# HLF356amp-revisi01.net
KiCad netlist of a schematic drawn in EAGLE
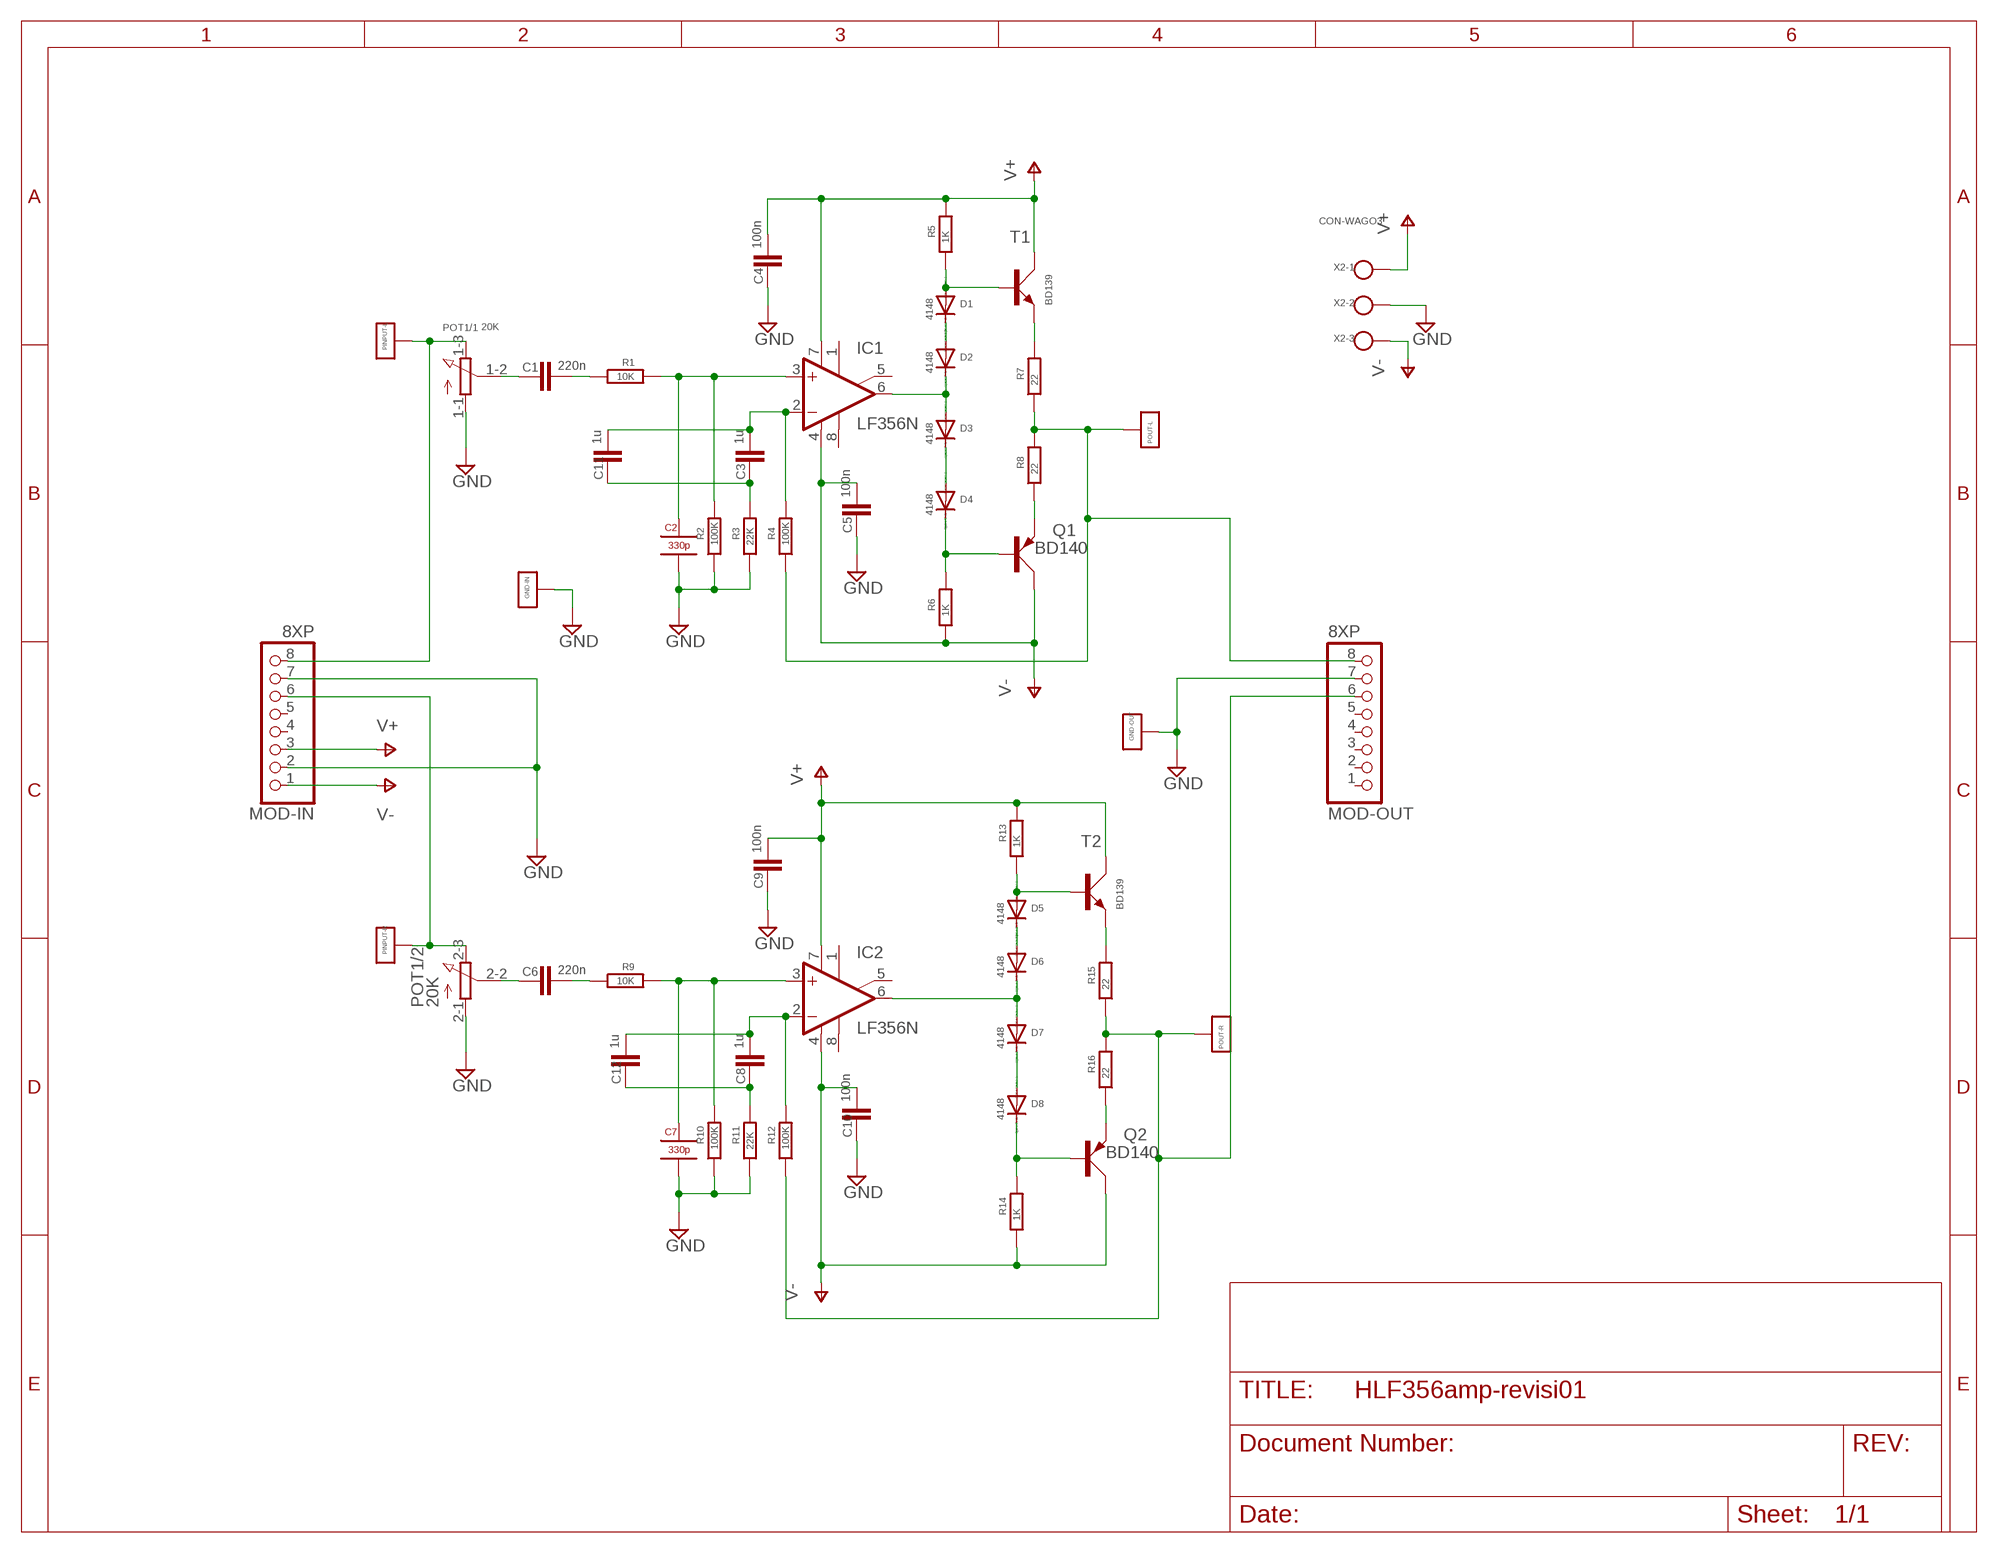
[diagram p0: schematic, sheet 1]

(export (version "E")
  (design (tool "Eeschema 10.0.6"))
  (components
    (comp (ref "C1")
      (value "220n")
      (footprint "eagle-import:C050-025X075")
      (libsource (lib "eagle-import") (part "C-EU050-025X075"))
    )
    (comp (ref "C2")
      (value "330p")
      (footprint "eagle-import:RIFAEVOX")
      (libsource (lib "eagle-import") (part "RIFAEVOXPFR5"))
    )
    (comp (ref "C3")
      (value "1u")
      (footprint "eagle-import:C150-072X183")
      (libsource (lib "eagle-import") (part "C-EU150-072X183"))
    )
    (comp (ref "C4")
      (value "100n")
      (footprint "eagle-import:C050-025X075")
      (libsource (lib "eagle-import") (part "C-EU050-025X075"))
    )
    (comp (ref "C5")
      (value "100n")
      (footprint "eagle-import:C050-025X075")
      (libsource (lib "eagle-import") (part "C-EU050-025X075"))
    )
    (comp (ref "C6")
      (value "220n")
      (footprint "eagle-import:C050-025X075")
      (libsource (lib "eagle-import") (part "C-EU050-025X075"))
    )
    (comp (ref "C7")
      (value "330p")
      (footprint "eagle-import:RIFAEVOX")
      (libsource (lib "eagle-import") (part "RIFAEVOXPFR5"))
    )
    (comp (ref "C8")
      (value "1u")
      (footprint "eagle-import:C150-072X183")
      (libsource (lib "eagle-import") (part "C-EU150-072X183"))
    )
    (comp (ref "C9")
      (value "100n")
      (footprint "eagle-import:C050-025X075")
      (libsource (lib "eagle-import") (part "C-EU050-025X075"))
    )
    (comp (ref "C10")
      (value "100n")
      (footprint "eagle-import:C050-025X075")
      (libsource (lib "eagle-import") (part "C-EU050-025X075"))
    )
    (comp (ref "C11")
      (value "1u")
      (footprint "eagle-import:C050-075X075")
      (libsource (lib "eagle-import") (part "C-EU050-075X075"))
    )
    (comp (ref "C12")
      (value "1u")
      (footprint "eagle-import:C050-075X075")
      (libsource (lib "eagle-import") (part "C-EU050-075X075"))
    )
    (comp (ref "D1")
      (value "4148")
      (footprint "eagle-import:DO35-7")
      (libsource (lib "eagle-import") (part "1N4148DO35-7"))
    )
    (comp (ref "D2")
      (value "4148")
      (footprint "eagle-import:DO35-7")
      (libsource (lib "eagle-import") (part "1N4148DO35-7"))
    )
    (comp (ref "D3")
      (value "4148")
      (footprint "eagle-import:DO35-7")
      (libsource (lib "eagle-import") (part "1N4148DO35-7"))
    )
    (comp (ref "D4")
      (value "4148")
      (footprint "eagle-import:DO35-7")
      (libsource (lib "eagle-import") (part "1N4148DO35-7"))
    )
    (comp (ref "D5")
      (value "4148")
      (footprint "eagle-import:DO35-7")
      (libsource (lib "eagle-import") (part "1N4148DO35-7"))
    )
    (comp (ref "D6")
      (value "4148")
      (footprint "eagle-import:DO35-7")
      (libsource (lib "eagle-import") (part "1N4148DO35-7"))
    )
    (comp (ref "D7")
      (value "4148")
      (footprint "eagle-import:DO35-7")
      (libsource (lib "eagle-import") (part "1N4148DO35-7"))
    )
    (comp (ref "D8")
      (value "4148")
      (footprint "eagle-import:DO35-7")
      (libsource (lib "eagle-import") (part "1N4148DO35-7"))
    )
    (comp (ref "GND-IN")
      (value "PIN-BIG1X")
      (footprint "eagle-import:PIN-BIG")
      (libsource (lib "eagle-import") (part "PIN-BIG1X"))
    )
    (comp (ref "GND-OUT")
      (value "PIN-BIG1X")
      (footprint "eagle-import:PIN-BIG")
      (libsource (lib "eagle-import") (part "PIN-BIG1X"))
    )
    (comp (ref "IC1")
      (value "LF356N")
      (footprint "eagle-import:DIL08")
      (libsource (lib "eagle-import") (part "LF356N"))
    )
    (comp (ref "IC2")
      (value "LF356N")
      (footprint "eagle-import:DIL08")
      (libsource (lib "eagle-import") (part "LF356N"))
    )
    (comp (ref "MOD-IN")
      (value "8XP")
      (footprint "eagle-import:1X08-BIG")
      (libsource (lib "eagle-import") (part "PINHD-1X8BIG"))
    )
    (comp (ref "MOD-OUT")
      (value "8XP")
      (footprint "eagle-import:1X08-BIG")
      (libsource (lib "eagle-import") (part "PINHD-1X8BIG"))
    )
    (comp (ref "PINPUT-L")
      (value "PIN-BIG1X")
      (footprint "eagle-import:PIN-BIG")
      (libsource (lib "eagle-import") (part "PIN-BIG1X"))
    )
    (comp (ref "PINPUT-R")
      (value "PIN-BIG1X")
      (footprint "eagle-import:PIN-BIG")
      (libsource (lib "eagle-import") (part "PIN-BIG1X"))
    )
    (comp (ref "POT1")
      (value "20K")
      (footprint "eagle-import:3RP_1610G")
      (libsource (lib "eagle-import") (part "3RP/1610G"))
    )
    (comp (ref "POUT-L")
      (value "PIN-BIG1X")
      (footprint "eagle-import:PIN-BIG")
      (libsource (lib "eagle-import") (part "PIN-BIG1X"))
    )
    (comp (ref "POUT-R")
      (value "PIN-BIG1X")
      (footprint "eagle-import:PIN-BIG")
      (libsource (lib "eagle-import") (part "PIN-BIG1X"))
    )
    (comp (ref "Q1")
      (value "BD140")
      (footprint "eagle-import:TO126AV")
      (libsource (lib "eagle-import") (part "BD140"))
    )
    (comp (ref "Q2")
      (value "BD140")
      (footprint "eagle-import:TO126AV")
      (libsource (lib "eagle-import") (part "BD140"))
    )
    (comp (ref "R1")
      (value "10K")
      (footprint "eagle-import:0204_7")
      (libsource (lib "eagle-import") (part "R-EU_0204/7"))
    )
    (comp (ref "R2")
      (value "100K")
      (footprint "eagle-import:0204_7")
      (libsource (lib "eagle-import") (part "R-EU_0204/7"))
    )
    (comp (ref "R3")
      (value "22K")
      (footprint "eagle-import:0204_7")
      (libsource (lib "eagle-import") (part "R-EU_0204/7"))
    )
    (comp (ref "R4")
      (value "100K")
      (footprint "eagle-import:0204_7")
      (libsource (lib "eagle-import") (part "R-EU_0204/7"))
    )
    (comp (ref "R5")
      (value "1K")
      (footprint "eagle-import:0204_7")
      (libsource (lib "eagle-import") (part "R-EU_0204/7"))
    )
    (comp (ref "R6")
      (value "1K")
      (footprint "eagle-import:0204_7")
      (libsource (lib "eagle-import") (part "R-EU_0204/7"))
    )
    (comp (ref "R7")
      (value "22")
      (footprint "eagle-import:0204_7")
      (libsource (lib "eagle-import") (part "R-EU_0204/7"))
    )
    (comp (ref "R8")
      (value "22")
      (footprint "eagle-import:0204_7")
      (libsource (lib "eagle-import") (part "R-EU_0204/7"))
    )
    (comp (ref "R9")
      (value "10K")
      (footprint "eagle-import:0204_7")
      (libsource (lib "eagle-import") (part "R-EU_0204/7"))
    )
    (comp (ref "R10")
      (value "100K")
      (footprint "eagle-import:0204_7")
      (libsource (lib "eagle-import") (part "R-EU_0204/7"))
    )
    (comp (ref "R11")
      (value "22K")
      (footprint "eagle-import:0204_7")
      (libsource (lib "eagle-import") (part "R-EU_0204/7"))
    )
    (comp (ref "R12")
      (value "100K")
      (footprint "eagle-import:0204_7")
      (libsource (lib "eagle-import") (part "R-EU_0204/7"))
    )
    (comp (ref "R13")
      (value "1K")
      (footprint "eagle-import:0204_7")
      (libsource (lib "eagle-import") (part "R-EU_0204/7"))
    )
    (comp (ref "R14")
      (value "1K")
      (footprint "eagle-import:0204_7")
      (libsource (lib "eagle-import") (part "R-EU_0204/7"))
    )
    (comp (ref "R15")
      (value "22")
      (footprint "eagle-import:0204_7")
      (libsource (lib "eagle-import") (part "R-EU_0204/7"))
    )
    (comp (ref "R16")
      (value "22")
      (footprint "eagle-import:0204_7")
      (libsource (lib "eagle-import") (part "R-EU_0204/7"))
    )
    (comp (ref "T1")
      (value "BD139")
      (footprint "eagle-import:TO126AV")
      (libsource (lib "eagle-import") (part "BD139"))
    )
    (comp (ref "T2")
      (value "BD139")
      (footprint "eagle-import:TO126AV")
      (libsource (lib "eagle-import") (part "BD139"))
    )
    (comp (ref "X2")
      (value "CON-WAGO3")
      (footprint "eagle-import:W237-103")
      (fields (field (name "MPN") "237-103"))
      (libsource (lib "eagle-import") (part "W237-103"))
    )
  )
  (nets
    (net (code "1") (name "GND") (class "Default")
      (node (ref "C10") (pin "1") (pinfunction "1_1") (pintype "passive"))
      (node (ref "C2") (pin "P$2") (pinfunction "P$2_P$2") (pintype "bidirectional"))
      (node (ref "C4") (pin "1") (pinfunction "1_1") (pintype "passive"))
      (node (ref "C5") (pin "1") (pinfunction "1_1") (pintype "passive"))
      (node (ref "C7") (pin "P$2") (pinfunction "P$2_P$2") (pintype "bidirectional"))
      (node (ref "C9") (pin "1") (pinfunction "1_1") (pintype "passive"))
      (node (ref "GND-IN") (pin "P$1") (pinfunction "P$1_P$1") (pintype "bidirectional"))
      (node (ref "GND-OUT") (pin "P$1") (pinfunction "P$1_P$1") (pintype "bidirectional"))
      (node (ref "MOD-IN") (pin "2") (pinfunction "2_2") (pintype "passive"))
      (node (ref "MOD-IN") (pin "7") (pinfunction "7_7") (pintype "passive"))
      (node (ref "MOD-OUT") (pin "7") (pinfunction "7_7") (pintype "passive"))
      (node (ref "POT1") (pin "1-1") (pinfunction "A_1-1") (pintype "passive"))
      (node (ref "POT1") (pin "2-1") (pinfunction "A_2-1") (pintype "passive"))
      (node (ref "R10") (pin "1") (pinfunction "1_1") (pintype "passive"))
      (node (ref "R11") (pin "1") (pinfunction "1_1") (pintype "passive"))
      (node (ref "R2") (pin "1") (pinfunction "1_1") (pintype "passive"))
      (node (ref "R3") (pin "1") (pinfunction "1_1") (pintype "passive"))
      (node (ref "X2") (pin "2") (pinfunction "KL_2") (pintype "passive"))
    )
    (net (code "2") (name "Net-(C1-Pad2)") (class "Default")
      (node (ref "C1") (pin "2") (pinfunction "2_2") (pintype "passive"))
      (node (ref "R1") (pin "1") (pinfunction "1_1") (pintype "passive"))
    )
    (net (code "3") (name "Net-(C6-Pad2)") (class "Default")
      (node (ref "C6") (pin "2") (pinfunction "2_2") (pintype "passive"))
      (node (ref "R9") (pin "1") (pinfunction "1_1") (pintype "passive"))
    )
    (net (code "4") (name "Net-(C11-Pad1)") (class "Default")
      (node (ref "C11") (pin "1") (pinfunction "1_1") (pintype "passive"))
      (node (ref "C3") (pin "1") (pinfunction "1_1") (pintype "passive"))
      (node (ref "R3") (pin "2") (pinfunction "2_2") (pintype "passive"))
    )
    (net (code "5") (name "Net-(C12-Pad1)") (class "Default")
      (node (ref "C12") (pin "1") (pinfunction "1_1") (pintype "passive"))
      (node (ref "C8") (pin "1") (pinfunction "1_1") (pintype "passive"))
      (node (ref "R11") (pin "2") (pinfunction "2_2") (pintype "passive"))
    )
    (net (code "6") (name "Net-(D1-PadA)") (class "Default")
      (node (ref "D1") (pin "A") (pinfunction "A_A") (pintype "passive"))
      (node (ref "R5") (pin "1") (pinfunction "1_1") (pintype "passive"))
      (node (ref "T1") (pin "B") (pinfunction "B_B") (pintype "passive"))
    )
    (net (code "7") (name "Net-(D1-PadC)") (class "Default")
      (node (ref "D1") (pin "C") (pinfunction "C_C") (pintype "passive"))
      (node (ref "D2") (pin "A") (pinfunction "A_A") (pintype "passive"))
    )
    (net (code "8") (name "Net-(D3-PadC)") (class "Default")
      (node (ref "D3") (pin "C") (pinfunction "C_C") (pintype "passive"))
      (node (ref "D4") (pin "A") (pinfunction "A_A") (pintype "passive"))
    )
    (net (code "9") (name "Net-(D4-PadC)") (class "Default")
      (node (ref "D4") (pin "C") (pinfunction "C_C") (pintype "passive"))
      (node (ref "Q1") (pin "B") (pinfunction "B_B") (pintype "passive"))
      (node (ref "R6") (pin "2") (pinfunction "2_2") (pintype "passive"))
    )
    (net (code "10") (name "Net-(D5-PadA)") (class "Default")
      (node (ref "D5") (pin "A") (pinfunction "A_A") (pintype "passive"))
      (node (ref "R13") (pin "1") (pinfunction "1_1") (pintype "passive"))
      (node (ref "T2") (pin "B") (pinfunction "B_B") (pintype "passive"))
    )
    (net (code "11") (name "Net-(D5-PadC)") (class "Default")
      (node (ref "D5") (pin "C") (pinfunction "C_C") (pintype "passive"))
      (node (ref "D6") (pin "A") (pinfunction "A_A") (pintype "passive"))
    )
    (net (code "12") (name "Net-(D7-PadC)") (class "Default")
      (node (ref "D7") (pin "C") (pinfunction "C_C") (pintype "passive"))
      (node (ref "D8") (pin "A") (pinfunction "A_A") (pintype "passive"))
    )
    (net (code "13") (name "Net-(D8-PadC)") (class "Default")
      (node (ref "D8") (pin "C") (pinfunction "C_C") (pintype "passive"))
      (node (ref "Q2") (pin "B") (pinfunction "B_B") (pintype "passive"))
      (node (ref "R14") (pin "2") (pinfunction "2_2") (pintype "passive"))
    )
    (net (code "14") (name "Net-(IC1-+IN)") (class "Default")
      (node (ref "C2") (pin "P$1") (pinfunction "P$1_P$1") (pintype "bidirectional"))
      (node (ref "IC1") (pin "3") (pinfunction "+IN_3") (pintype "input"))
      (node (ref "R1") (pin "2") (pinfunction "2_2") (pintype "passive"))
      (node (ref "R2") (pin "2") (pinfunction "2_2") (pintype "passive"))
    )
    (net (code "15") (name "Net-(IC1--IN)") (class "Default")
      (node (ref "C11") (pin "2") (pinfunction "2_2") (pintype "passive"))
      (node (ref "C3") (pin "2") (pinfunction "2_2") (pintype "passive"))
      (node (ref "IC1") (pin "2") (pinfunction "-IN_2") (pintype "input"))
      (node (ref "R4") (pin "2") (pinfunction "2_2") (pintype "passive"))
    )
    (net (code "16") (name "Net-(IC1-OUT)") (class "Default")
      (node (ref "D2") (pin "C") (pinfunction "C_C") (pintype "passive"))
      (node (ref "D3") (pin "A") (pinfunction "A_A") (pintype "passive"))
      (node (ref "IC1") (pin "6") (pinfunction "OUT_6") (pintype "output"))
    )
    (net (code "17") (name "Net-(IC2-+IN)") (class "Default")
      (node (ref "C7") (pin "P$1") (pinfunction "P$1_P$1") (pintype "bidirectional"))
      (node (ref "IC2") (pin "3") (pinfunction "+IN_3") (pintype "input"))
      (node (ref "R10") (pin "2") (pinfunction "2_2") (pintype "passive"))
      (node (ref "R9") (pin "2") (pinfunction "2_2") (pintype "passive"))
    )
    (net (code "18") (name "Net-(IC2--IN)") (class "Default")
      (node (ref "C12") (pin "2") (pinfunction "2_2") (pintype "passive"))
      (node (ref "C8") (pin "2") (pinfunction "2_2") (pintype "passive"))
      (node (ref "IC2") (pin "2") (pinfunction "-IN_2") (pintype "input"))
      (node (ref "R12") (pin "2") (pinfunction "2_2") (pintype "passive"))
    )
    (net (code "19") (name "Net-(IC2-OUT)") (class "Default")
      (node (ref "D6") (pin "C") (pinfunction "C_C") (pintype "passive"))
      (node (ref "D7") (pin "A") (pinfunction "A_A") (pintype "passive"))
      (node (ref "IC2") (pin "6") (pinfunction "OUT_6") (pintype "output"))
    )
    (net (code "20") (name "Net-(MOD-OUT-Pad6)") (class "Default")
      (node (ref "MOD-OUT") (pin "6") (pinfunction "6_6") (pintype "passive"))
      (node (ref "POUT-R") (pin "P$1") (pinfunction "P$1_P$1") (pintype "bidirectional"))
      (node (ref "R12") (pin "1") (pinfunction "1_1") (pintype "passive"))
      (node (ref "R15") (pin "1") (pinfunction "1_1") (pintype "passive"))
      (node (ref "R16") (pin "2") (pinfunction "2_2") (pintype "passive"))
    )
    (net (code "21") (name "Net-(MOD-OUT-Pad8)") (class "Default")
      (node (ref "MOD-OUT") (pin "8") (pinfunction "8_8") (pintype "passive"))
      (node (ref "POUT-L") (pin "P$1") (pinfunction "P$1_P$1") (pintype "bidirectional"))
      (node (ref "R4") (pin "1") (pinfunction "1_1") (pintype "passive"))
      (node (ref "R7") (pin "1") (pinfunction "1_1") (pintype "passive"))
      (node (ref "R8") (pin "2") (pinfunction "2_2") (pintype "passive"))
    )
    (net (code "22") (name "Net-(POT1A-E)") (class "Default")
      (node (ref "MOD-IN") (pin "8") (pinfunction "8_8") (pintype "passive"))
      (node (ref "PINPUT-L") (pin "P$1") (pinfunction "P$1_P$1") (pintype "bidirectional"))
      (node (ref "POT1") (pin "1-3") (pinfunction "E_1-3") (pintype "passive"))
    )
    (net (code "23") (name "Net-(POT1A-S)") (class "Default")
      (node (ref "C1") (pin "1") (pinfunction "1_1") (pintype "passive"))
      (node (ref "POT1") (pin "1-2") (pinfunction "S_1-2") (pintype "passive"))
    )
    (net (code "24") (name "Net-(POT1B-E)") (class "Default")
      (node (ref "MOD-IN") (pin "6") (pinfunction "6_6") (pintype "passive"))
      (node (ref "PINPUT-R") (pin "P$1") (pinfunction "P$1_P$1") (pintype "bidirectional"))
      (node (ref "POT1") (pin "2-3") (pinfunction "E_2-3") (pintype "passive"))
    )
    (net (code "25") (name "Net-(POT1B-S)") (class "Default")
      (node (ref "C6") (pin "1") (pinfunction "1_1") (pintype "passive"))
      (node (ref "POT1") (pin "2-2") (pinfunction "S_2-2") (pintype "passive"))
    )
    (net (code "26") (name "Net-(Q1-PadE)") (class "Default")
      (node (ref "Q1") (pin "E") (pinfunction "E_E") (pintype "passive"))
      (node (ref "R8") (pin "1") (pinfunction "1_1") (pintype "passive"))
    )
    (net (code "27") (name "Net-(Q2-PadE)") (class "Default")
      (node (ref "Q2") (pin "E") (pinfunction "E_E") (pintype "passive"))
      (node (ref "R16") (pin "1") (pinfunction "1_1") (pintype "passive"))
    )
    (net (code "28") (name "Net-(R7-Pad2)") (class "Default")
      (node (ref "R7") (pin "2") (pinfunction "2_2") (pintype "passive"))
      (node (ref "T1") (pin "E") (pinfunction "E_E") (pintype "passive"))
    )
    (net (code "29") (name "Net-(R15-Pad2)") (class "Default")
      (node (ref "R15") (pin "2") (pinfunction "2_2") (pintype "passive"))
      (node (ref "T2") (pin "E") (pinfunction "E_E") (pintype "passive"))
    )
    (net (code "30") (name "V+") (class "Default")
      (node (ref "C4") (pin "2") (pinfunction "2_2") (pintype "passive"))
      (node (ref "C9") (pin "2") (pinfunction "2_2") (pintype "passive"))
      (node (ref "IC1") (pin "7") (pinfunction "V+_7") (pintype "power_in"))
      (node (ref "IC2") (pin "7") (pinfunction "V+_7") (pintype "power_in"))
      (node (ref "MOD-IN") (pin "3") (pinfunction "3_3") (pintype "passive"))
      (node (ref "R13") (pin "2") (pinfunction "2_2") (pintype "passive"))
      (node (ref "R5") (pin "2") (pinfunction "2_2") (pintype "passive"))
      (node (ref "T1") (pin "C") (pinfunction "C_C") (pintype "passive"))
      (node (ref "T2") (pin "C") (pinfunction "C_C") (pintype "passive"))
      (node (ref "X2") (pin "1") (pinfunction "KL_1") (pintype "passive"))
    )
    (net (code "31") (name "V-") (class "Default")
      (node (ref "C10") (pin "2") (pinfunction "2_2") (pintype "passive"))
      (node (ref "C5") (pin "2") (pinfunction "2_2") (pintype "passive"))
      (node (ref "IC1") (pin "4") (pinfunction "V-_4") (pintype "power_in"))
      (node (ref "IC2") (pin "4") (pinfunction "V-_4") (pintype "power_in"))
      (node (ref "MOD-IN") (pin "1") (pinfunction "1_1") (pintype "passive"))
      (node (ref "Q1") (pin "C") (pinfunction "C_C") (pintype "passive"))
      (node (ref "Q2") (pin "C") (pinfunction "C_C") (pintype "passive"))
      (node (ref "R14") (pin "1") (pinfunction "1_1") (pintype "passive"))
      (node (ref "R6") (pin "1") (pinfunction "1_1") (pintype "passive"))
      (node (ref "X2") (pin "3") (pinfunction "KL_3") (pintype "passive"))
    )
    (net (code "32") (name "unconnected-(IC1-ON1-Pad1)") (class "Default")
      (node (ref "IC1") (pin "1") (pinfunction "ON1_1") (pintype "passive"))
    )
    (net (code "33") (name "unconnected-(IC1-ON2-Pad5)") (class "Default")
      (node (ref "IC1") (pin "5") (pinfunction "ON2_5") (pintype "passive"))
    )
    (net (code "34") (name "unconnected-(IC1-OPT-Pad8)") (class "Default")
      (node (ref "IC1") (pin "8") (pinfunction "OPT_8") (pintype "passive"))
    )
    (net (code "35") (name "unconnected-(IC2-ON1-Pad1)") (class "Default")
      (node (ref "IC2") (pin "1") (pinfunction "ON1_1") (pintype "passive"))
    )
    (net (code "36") (name "unconnected-(IC2-ON2-Pad5)") (class "Default")
      (node (ref "IC2") (pin "5") (pinfunction "ON2_5") (pintype "passive"))
    )
    (net (code "37") (name "unconnected-(IC2-OPT-Pad8)") (class "Default")
      (node (ref "IC2") (pin "8") (pinfunction "OPT_8") (pintype "passive"))
    )
    (net (code "38") (name "unconnected-(MOD-IN-Pad4)") (class "Default")
      (node (ref "MOD-IN") (pin "4") (pinfunction "4_4") (pintype "passive"))
    )
    (net (code "39") (name "unconnected-(MOD-IN-Pad5)") (class "Default")
      (node (ref "MOD-IN") (pin "5") (pinfunction "5_5") (pintype "passive"))
    )
    (net (code "40") (name "unconnected-(MOD-OUT-Pad1)") (class "Default")
      (node (ref "MOD-OUT") (pin "1") (pinfunction "1_1") (pintype "passive"))
    )
    (net (code "41") (name "unconnected-(MOD-OUT-Pad2)") (class "Default")
      (node (ref "MOD-OUT") (pin "2") (pinfunction "2_2") (pintype "passive"))
    )
    (net (code "42") (name "unconnected-(MOD-OUT-Pad3)") (class "Default")
      (node (ref "MOD-OUT") (pin "3") (pinfunction "3_3") (pintype "passive"))
    )
    (net (code "43") (name "unconnected-(MOD-OUT-Pad4)") (class "Default")
      (node (ref "MOD-OUT") (pin "4") (pinfunction "4_4") (pintype "passive"))
    )
    (net (code "44") (name "unconnected-(MOD-OUT-Pad5)") (class "Default")
      (node (ref "MOD-OUT") (pin "5") (pinfunction "5_5") (pintype "passive"))
    )
  )
)
